# RF1.net
KiCad netlist of a schematic drawn in EAGLE
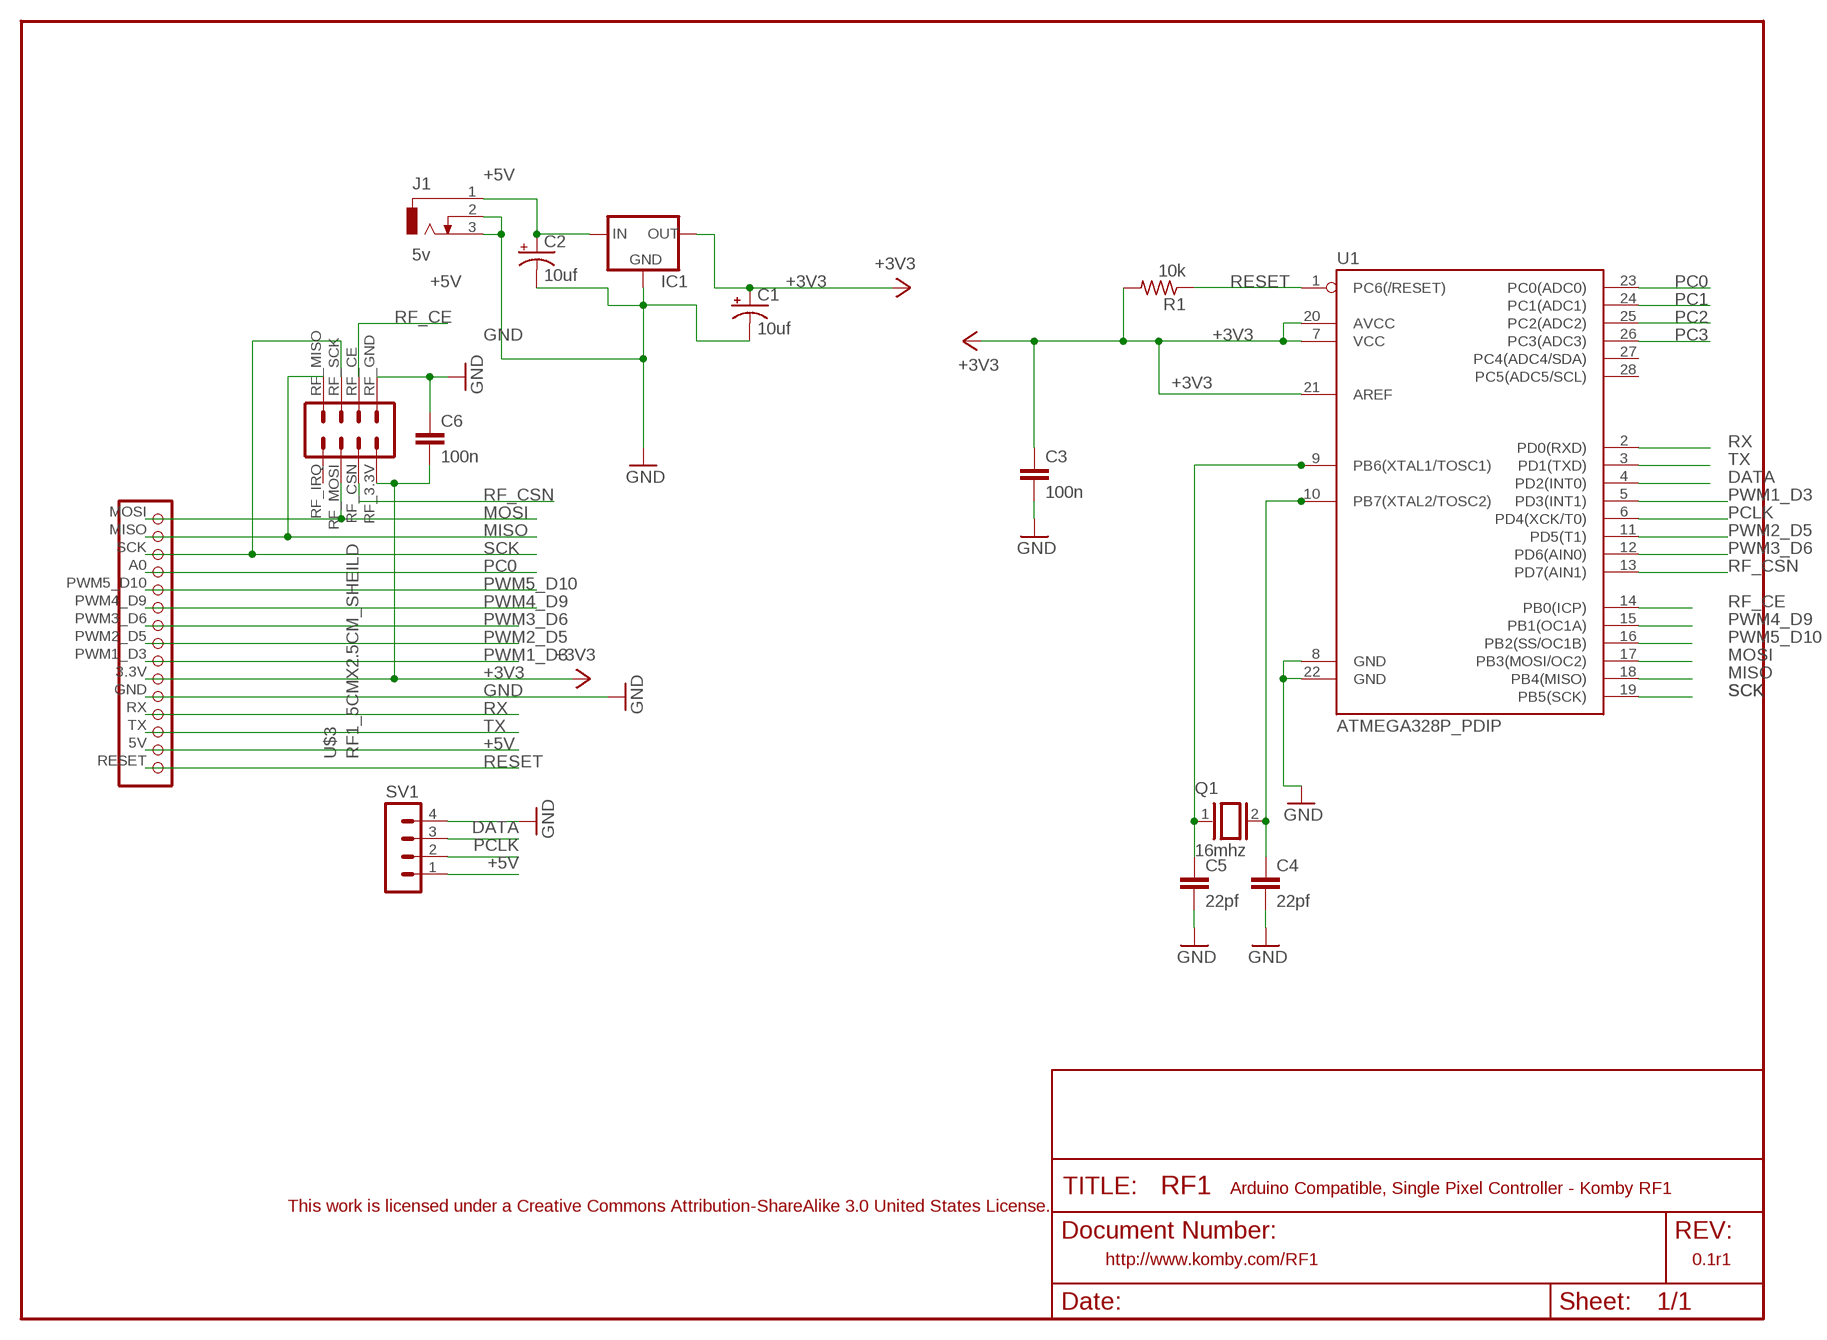
[diagram p0: schematic, sheet 1]

(export (version "E")
  (design (tool "Eeschema 10.0.6"))
  (components
    (comp (ref "C1")
      (value "10uf")
      (footprint "eagle-import:E1,8-4")
      (libsource (lib "eagle-import") (part "CPOL-USE1.8-4"))
    )
    (comp (ref "C2")
      (value "10uf")
      (footprint "eagle-import:E1,8-4")
      (libsource (lib "eagle-import") (part "CPOL-USE1.8-4"))
    )
    (comp (ref "C3")
      (value "100n")
      (footprint "eagle-import:C025-024X044")
      (libsource (lib "eagle-import") (part "C-EU025-024X044"))
    )
    (comp (ref "C4")
      (value "22pf")
      (footprint "eagle-import:C025-024X044")
      (libsource (lib "eagle-import") (part "C-EU025-024X044"))
    )
    (comp (ref "C5")
      (value "22pf")
      (footprint "eagle-import:C025-024X044")
      (libsource (lib "eagle-import") (part "C-EU025-024X044"))
    )
    (comp (ref "C6")
      (value "100n")
      (footprint "eagle-import:C025-024X044")
      (libsource (lib "eagle-import") (part "C-EU025-024X044"))
    )
    (comp (ref "IC1")
      (value "MCP1700TRI")
      (footprint "eagle-import:TO92")
      (libsource (lib "eagle-import") (part "MCP1700TRI"))
    )
    (comp (ref "J1")
      (value "5v")
      (footprint "eagle-import:DCJ0303")
      (libsource (lib "eagle-import") (part "DCJ0303"))
    )
    (comp (ref "Q1")
      (value "16mhz")
      (footprint "eagle-import:QS")
      (libsource (lib "eagle-import") (part "XTAL/S"))
    )
    (comp (ref "R1")
      (value "10k")
      (footprint "eagle-import:0207_7")
      (libsource (lib "eagle-import") (part "R-US_0207/7"))
    )
    (comp (ref "SV1")
      (value "MA04-1")
      (footprint "eagle-import:MA04-1")
      (libsource (lib "eagle-import") (part "MA04-1"))
    )
    (comp (ref "U$3")
      (value "RF1_5CMX2.5CM_SHEILD")
      (footprint "eagle-import:KOMBY_RF1_SHEILD_5X2.5")
      (libsource (lib "eagle-import") (part "RF1_5CMX2.5CM_SHEILD"))
    )
    (comp (ref "U1")
      (value "ATMEGA328P_PDIP")
      (footprint "eagle-import:DIL28-3")
      (libsource (lib "eagle-import") (part "ATMEGA328P_PDIP"))
    )
  )
  (nets
    (net (code "1") (name "+3V3") (class "Default")
      (node (ref "C1") (pin "+") (pinfunction "+_+") (pintype "passive"))
      (node (ref "C3") (pin "1") (pinfunction "1_1") (pintype "passive"))
      (node (ref "C6") (pin "2") (pinfunction "2_2") (pintype "passive"))
      (node (ref "IC1") (pin "3") (pinfunction "OUT_3") (pintype "passive"))
      (node (ref "R1") (pin "2") (pinfunction "2_2") (pintype "passive"))
      (node (ref "U$3") (pin "3.3V") (pinfunction "3.3V_3.3V") (pintype "passive"))
      (node (ref "U$3") (pin "RF_3.3V") (pinfunction "RF_3.3V_RF_3.3V") (pintype "passive"))
      (node (ref "U1") (pin "20") (pinfunction "AVCC_20") (pintype "bidirectional"))
      (node (ref "U1") (pin "21") (pinfunction "AREF_21") (pintype "bidirectional"))
      (node (ref "U1") (pin "7") (pinfunction "VCC_7") (pintype "bidirectional"))
    )
    (net (code "2") (name "/+5V") (class "Default")
      (node (ref "C2") (pin "+") (pinfunction "+_+") (pintype "passive"))
      (node (ref "IC1") (pin "2") (pinfunction "IN_2") (pintype "input"))
      (node (ref "J1") (pin "1") (pinfunction "1_1") (pintype "passive"))
      (node (ref "SV1") (pin "1") (pinfunction "1_1") (pintype "passive"))
      (node (ref "U$3") (pin "5V") (pinfunction "5V_5V") (pintype "passive"))
    )
    (net (code "3") (name "/DATA") (class "Default")
      (node (ref "SV1") (pin "3") (pinfunction "3_3") (pintype "passive"))
      (node (ref "U1") (pin "4") (pinfunction "PD2(INT0)_4") (pintype "bidirectional"))
    )
    (net (code "4") (name "/MISO") (class "Default")
      (node (ref "U$3") (pin "MISO") (pinfunction "MISO_MISO") (pintype "passive"))
      (node (ref "U$3") (pin "RF_MISO") (pinfunction "RF_MISO_RF_MISO") (pintype "passive"))
      (node (ref "U1") (pin "18") (pinfunction "PB4(MISO)_18") (pintype "bidirectional"))
    )
    (net (code "5") (name "/MOSI") (class "Default")
      (node (ref "U$3") (pin "MOSI") (pinfunction "MOSI_MOSI") (pintype "passive"))
      (node (ref "U$3") (pin "RF_MOSI") (pinfunction "RF_MOSI_RF_MOSI") (pintype "passive"))
      (node (ref "U1") (pin "17") (pinfunction "PB3(MOSI/OC2)_17") (pintype "bidirectional"))
    )
    (net (code "6") (name "/PC0") (class "Default")
      (node (ref "U$3") (pin "A0") (pinfunction "PC0_A0") (pintype "passive"))
      (node (ref "U1") (pin "23") (pinfunction "PC0(ADC0)_23") (pintype "bidirectional"))
    )
    (net (code "7") (name "/PC1") (class "Default")
      (node (ref "U1") (pin "24") (pinfunction "PC1(ADC1)_24") (pintype "bidirectional"))
    )
    (net (code "8") (name "/PC2") (class "Default")
      (node (ref "U1") (pin "25") (pinfunction "PC2(ADC2)_25") (pintype "bidirectional"))
    )
    (net (code "9") (name "/PC3") (class "Default")
      (node (ref "U1") (pin "26") (pinfunction "PC3(ADC3)_26") (pintype "bidirectional"))
    )
    (net (code "10") (name "/PCLK") (class "Default")
      (node (ref "SV1") (pin "2") (pinfunction "2_2") (pintype "passive"))
      (node (ref "U1") (pin "6") (pinfunction "PD4(XCK/T0)_6") (pintype "bidirectional"))
    )
    (net (code "11") (name "/PWM1_D3") (class "Default")
      (node (ref "U$3") (pin "PWM1_D3") (pinfunction "PWM1_PWM1_D3") (pintype "passive"))
      (node (ref "U1") (pin "5") (pinfunction "PD3(INT1)_5") (pintype "bidirectional"))
    )
    (net (code "12") (name "/PWM2_D5") (class "Default")
      (node (ref "U$3") (pin "PWM2_D5") (pinfunction "PWM2_PWM2_D5") (pintype "passive"))
      (node (ref "U1") (pin "11") (pinfunction "PD5(T1)_11") (pintype "bidirectional"))
    )
    (net (code "13") (name "/PWM3_D6") (class "Default")
      (node (ref "U$3") (pin "PWM3_D6") (pinfunction "PWM3_PWM3_D6") (pintype "passive"))
      (node (ref "U1") (pin "12") (pinfunction "PD6(AIN0)_12") (pintype "bidirectional"))
    )
    (net (code "14") (name "/PWM4_D9") (class "Default")
      (node (ref "U$3") (pin "PWM4_D9") (pinfunction "PWM4_PWM4_D9") (pintype "passive"))
      (node (ref "U1") (pin "15") (pinfunction "PB1(OC1A)_15") (pintype "bidirectional"))
    )
    (net (code "15") (name "/PWM5_D10") (class "Default")
      (node (ref "U$3") (pin "PWM5_D10") (pinfunction "PWM5_PWM5_D10") (pintype "passive"))
      (node (ref "U1") (pin "16") (pinfunction "PB2(SS/OC1B)_16") (pintype "bidirectional"))
    )
    (net (code "16") (name "/RESET") (class "Default")
      (node (ref "R1") (pin "1") (pinfunction "1_1") (pintype "passive"))
      (node (ref "U$3") (pin "RESET") (pinfunction "RESET_RESET") (pintype "passive"))
      (node (ref "U1") (pin "1") (pinfunction "PC6(/RESET)_1") (pintype "bidirectional"))
    )
    (net (code "17") (name "/RF_CE") (class "Default")
      (node (ref "U$3") (pin "RF_CE") (pinfunction "RF_CE_RF_CE") (pintype "passive"))
      (node (ref "U1") (pin "14") (pinfunction "PB0(ICP)_14") (pintype "bidirectional"))
    )
    (net (code "18") (name "/RF_CSN") (class "Default")
      (node (ref "U$3") (pin "RF_CSN") (pinfunction "RF_CSN_RF_CSN") (pintype "passive"))
      (node (ref "U1") (pin "13") (pinfunction "PD7(AIN1)_13") (pintype "bidirectional"))
    )
    (net (code "19") (name "/RX") (class "Default")
      (node (ref "U$3") (pin "RX") (pinfunction "RX_RX") (pintype "passive"))
      (node (ref "U1") (pin "2") (pinfunction "PD0(RXD)_2") (pintype "bidirectional"))
    )
    (net (code "20") (name "/SCK") (class "Default")
      (node (ref "U$3") (pin "RF_SCK") (pinfunction "RF_SCK_RF_SCK") (pintype "passive"))
      (node (ref "U$3") (pin "SCK") (pinfunction "SCK_SCK") (pintype "passive"))
      (node (ref "U1") (pin "19") (pinfunction "PB5(SCK)_19") (pintype "bidirectional"))
    )
    (net (code "21") (name "/TX") (class "Default")
      (node (ref "U$3") (pin "TX") (pinfunction "TX_TX") (pintype "passive"))
      (node (ref "U1") (pin "3") (pinfunction "PD1(TXD)_3") (pintype "bidirectional"))
    )
    (net (code "22") (name "GND") (class "Default")
      (node (ref "C1") (pin "-") (pinfunction "-_-") (pintype "passive"))
      (node (ref "C2") (pin "-") (pinfunction "-_-") (pintype "passive"))
      (node (ref "C3") (pin "2") (pinfunction "2_2") (pintype "passive"))
      (node (ref "C4") (pin "2") (pinfunction "2_2") (pintype "passive"))
      (node (ref "C5") (pin "2") (pinfunction "2_2") (pintype "passive"))
      (node (ref "C6") (pin "1") (pinfunction "1_1") (pintype "passive"))
      (node (ref "IC1") (pin "1") (pinfunction "GND_1") (pintype "input"))
      (node (ref "J1") (pin "2") (pinfunction "2_2") (pintype "passive"))
      (node (ref "J1") (pin "3") (pinfunction "3_3") (pintype "passive"))
      (node (ref "SV1") (pin "4") (pinfunction "4_4") (pintype "passive"))
      (node (ref "U$3") (pin "GND") (pinfunction "GND_GND") (pintype "passive"))
      (node (ref "U$3") (pin "RF_GND") (pinfunction "RFGND_1_RF_GND") (pintype "passive"))
      (node (ref "U1") (pin "22") (pinfunction "GND_22") (pintype "bidirectional"))
      (node (ref "U1") (pin "8") (pinfunction "GND_8") (pintype "bidirectional"))
    )
    (net (code "23") (name "Net-(U1-PB6(XTAL1{slash}TOSC1))") (class "Default")
      (node (ref "C5") (pin "1") (pinfunction "1_1") (pintype "passive"))
      (node (ref "Q1") (pin "1") (pinfunction "1_1") (pintype "passive"))
      (node (ref "U1") (pin "9") (pinfunction "PB6(XTAL1/TOSC1)_9") (pintype "bidirectional"))
    )
    (net (code "24") (name "Net-(U1-PB7(XTAL2{slash}TOSC2))") (class "Default")
      (node (ref "C4") (pin "1") (pinfunction "1_1") (pintype "passive"))
      (node (ref "Q1") (pin "2") (pinfunction "2_2") (pintype "passive"))
      (node (ref "U1") (pin "10") (pinfunction "PB7(XTAL2/TOSC2)_10") (pintype "bidirectional"))
    )
    (net (code "25") (name "unconnected-(U$3-PadRF_IRQ)") (class "Default")
      (node (ref "U$3") (pin "RF_IRQ") (pinfunction "RF_IRQ_RF_IRQ") (pintype "passive"))
    )
    (net (code "26") (name "unconnected-(U1-PC4(ADC4{slash}SDA)-Pad27)") (class "Default")
      (node (ref "U1") (pin "27") (pinfunction "PC4(ADC4/SDA)_27") (pintype "bidirectional"))
    )
    (net (code "27") (name "unconnected-(U1-PC5(ADC5{slash}SCL)-Pad28)") (class "Default")
      (node (ref "U1") (pin "28") (pinfunction "PC5(ADC5/SCL)_28") (pintype "bidirectional"))
    )
  )
)
